# Bolt.net
KiCad netlist of a schematic drawn in EAGLE
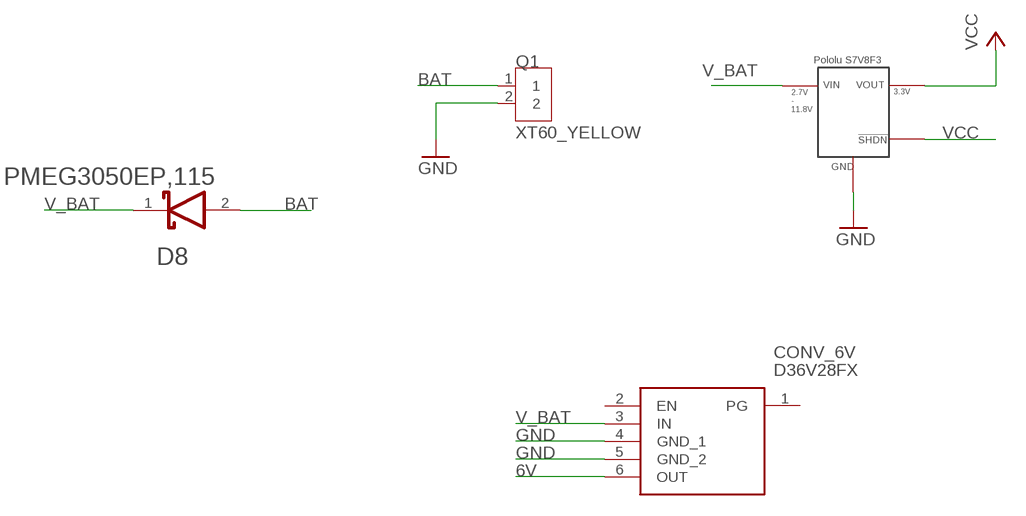
[diagram p0: schematic, sheet 1]
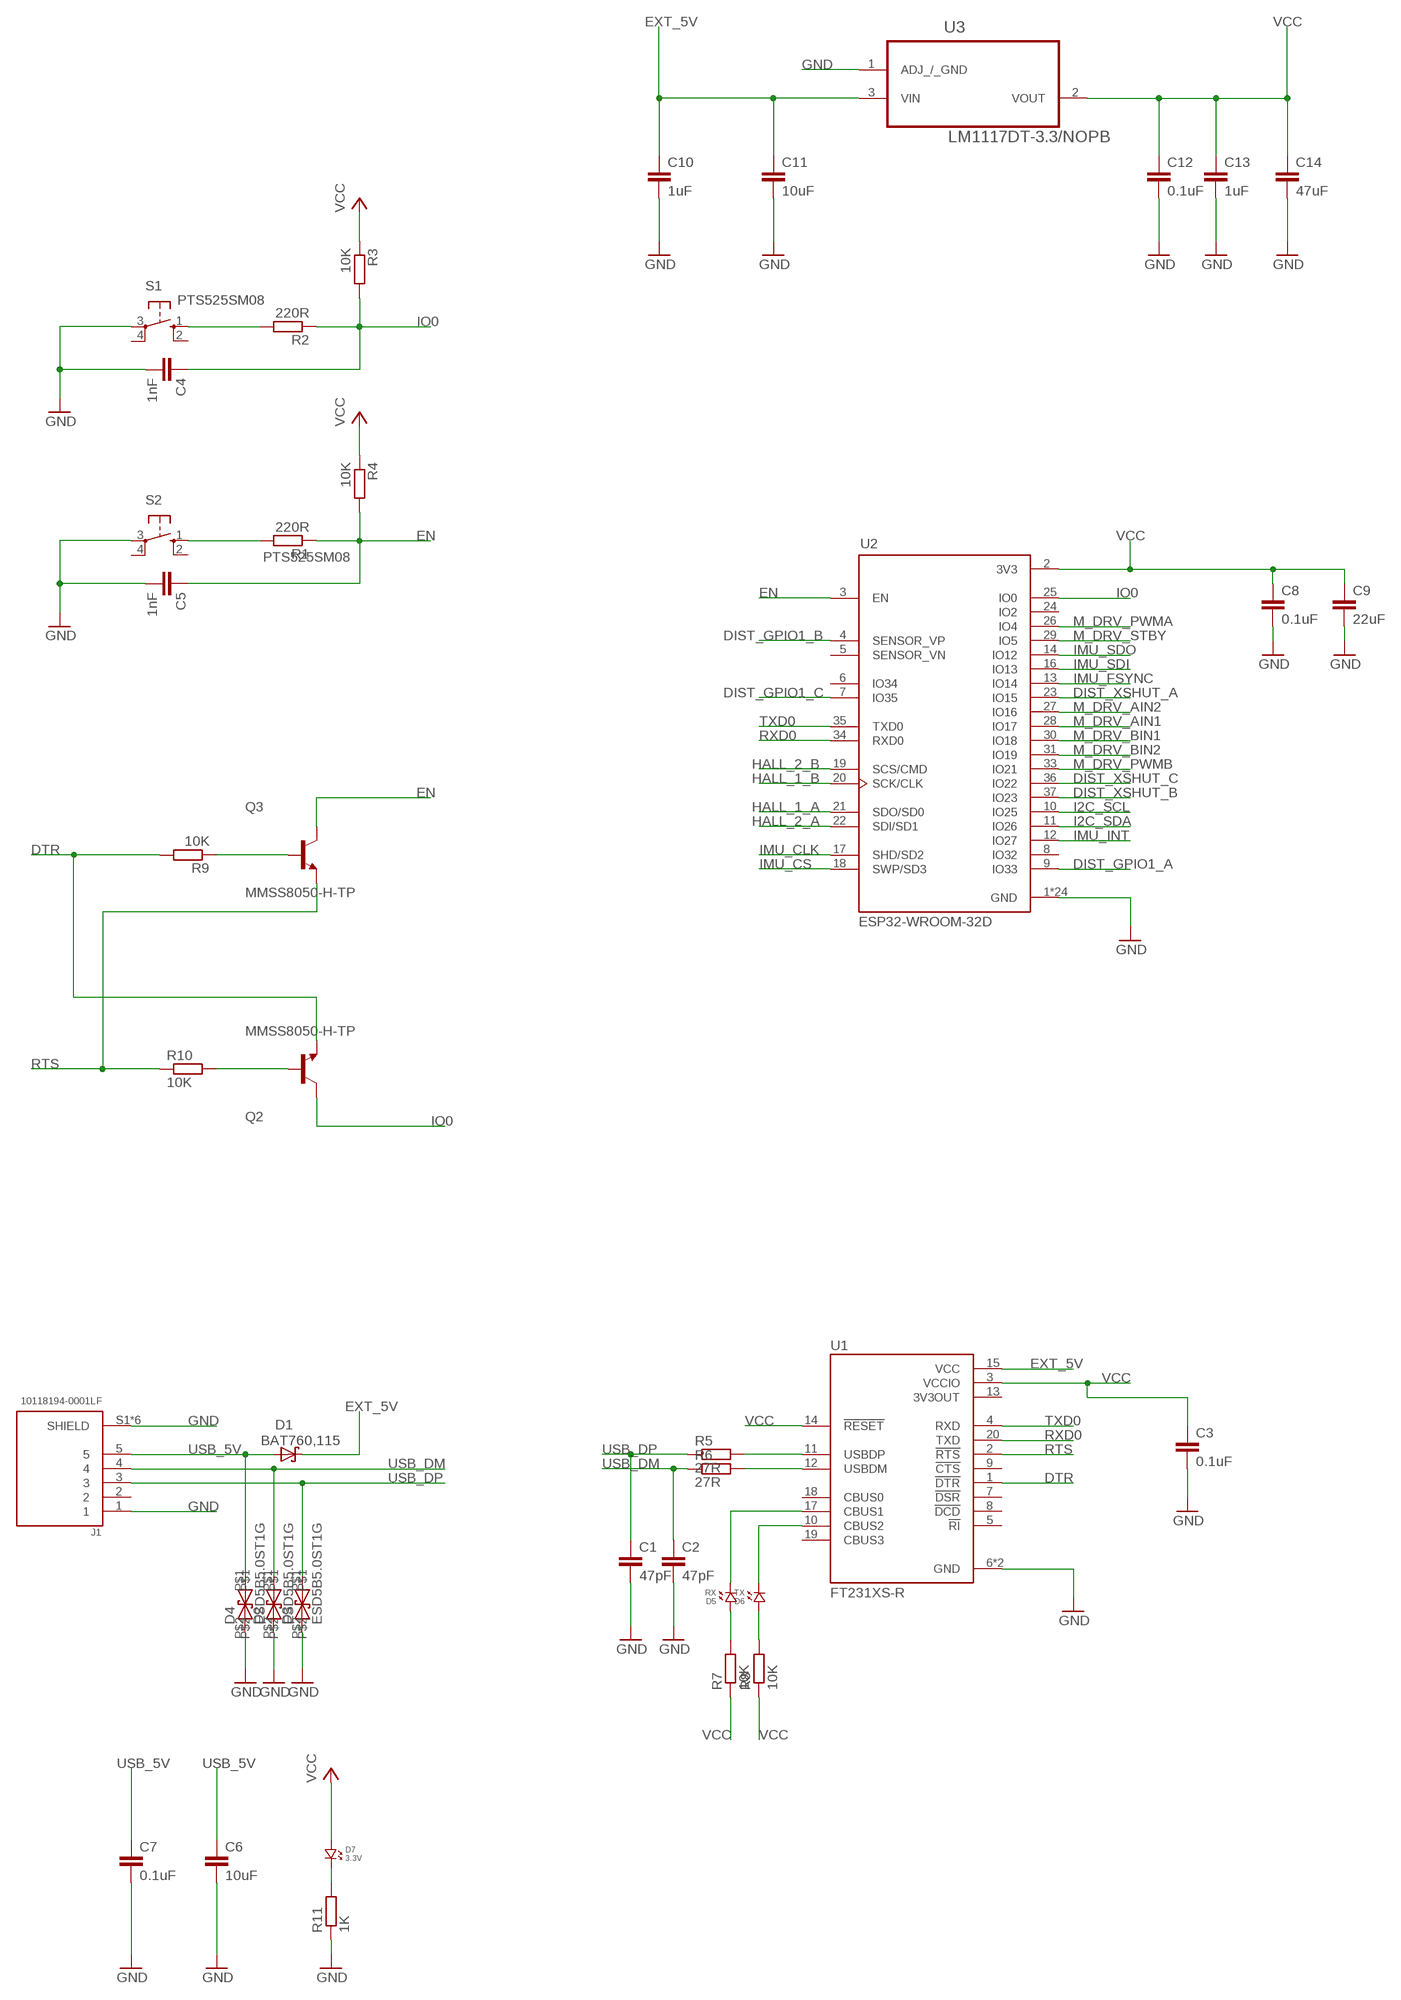
[diagram p1: schematic, sheet 2]
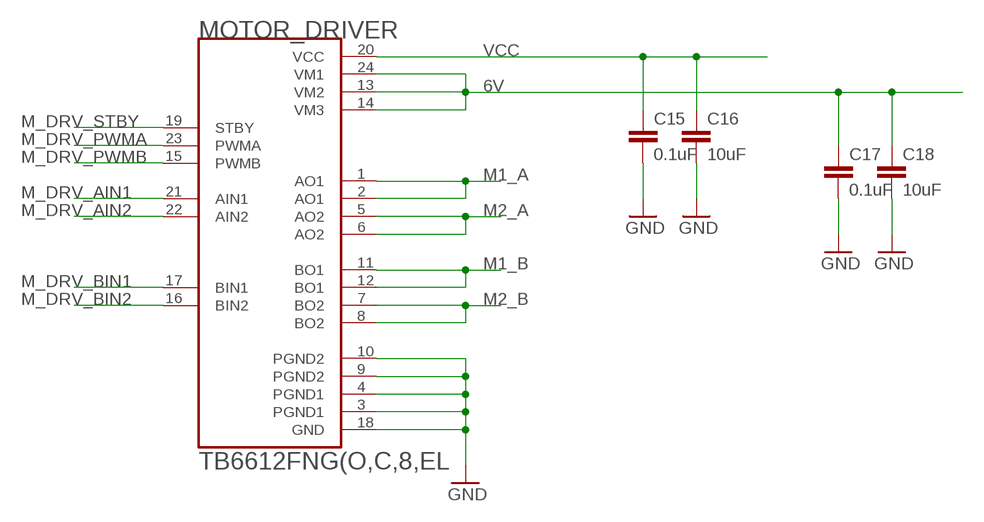
[diagram p2: schematic, sheet 3]
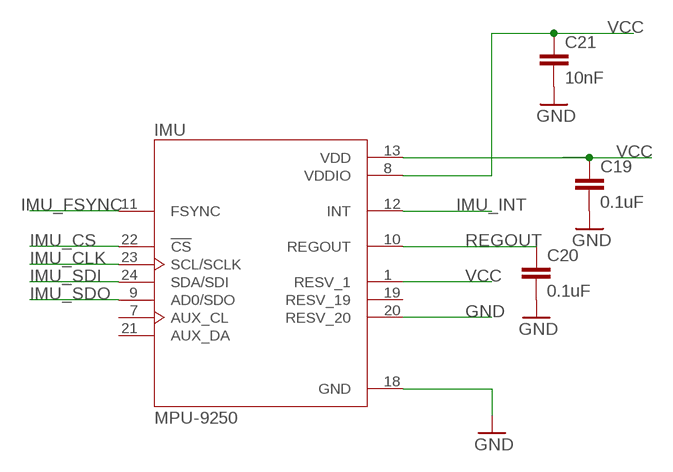
[diagram p3: schematic, sheet 4]
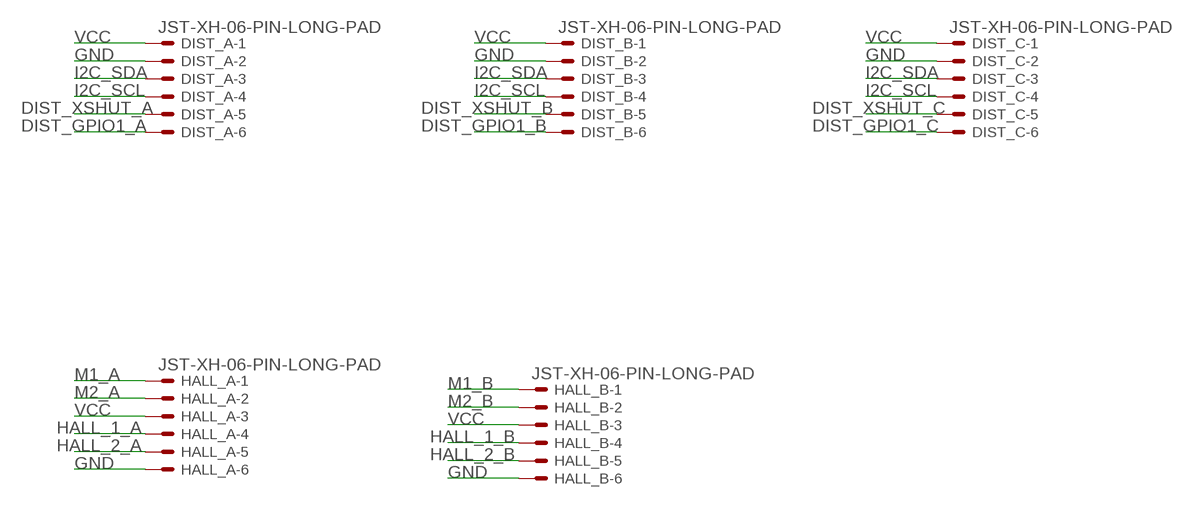
[diagram p4: schematic, sheet 5]

(export (version "E")
  (design (tool "Eeschema 10.0.6"))
  (components
    (comp (ref "DIST_A")
      (value "JST-XH-06-PIN-LONG-PAD")
      (footprint "eagle-import:JST-XH-06-PACKAGE-LONG-PAD")
      (libsource (lib "eagle-import") (part "JST-XH-06-PIN-LONG-PAD"))
    )
    (comp (ref "DIST_B")
      (value "JST-XH-06-PIN-LONG-PAD")
      (footprint "eagle-import:JST-XH-06-PACKAGE-LONG-PAD")
      (libsource (lib "eagle-import") (part "JST-XH-06-PIN-LONG-PAD"))
    )
    (comp (ref "DIST_C")
      (value "JST-XH-06-PIN-LONG-PAD")
      (footprint "eagle-import:JST-XH-06-PACKAGE-LONG-PAD")
      (libsource (lib "eagle-import") (part "JST-XH-06-PIN-LONG-PAD"))
    )
    (comp (ref "HALL_A")
      (value "JST-XH-06-PIN-LONG-PAD")
      (footprint "eagle-import:JST-XH-06-PACKAGE-LONG-PAD")
      (libsource (lib "eagle-import") (part "JST-XH-06-PIN-LONG-PAD"))
    )
    (comp (ref "HALL_B")
      (value "JST-XH-06-PIN-LONG-PAD")
      (footprint "eagle-import:JST-XH-06-PACKAGE-LONG-PAD")
      (libsource (lib "eagle-import") (part "JST-XH-06-PIN-LONG-PAD"))
    )
    (comp (ref "C1")
      (value "47pF")
      (footprint "eagle-import:C0805K")
      (libsource (lib "eagle-import") (part "C-EUC0805K"))
    )
    (comp (ref "C2")
      (value "47pF")
      (footprint "eagle-import:C0805K")
      (libsource (lib "eagle-import") (part "C-EUC0805K"))
    )
    (comp (ref "C3")
      (value "0.1uF")
      (footprint "eagle-import:C0805K")
      (libsource (lib "eagle-import") (part "C-EUC0805K"))
    )
    (comp (ref "C4")
      (value "1nF")
      (footprint "eagle-import:C0805K")
      (libsource (lib "eagle-import") (part "C-EUC0805K"))
    )
    (comp (ref "C5")
      (value "1nF")
      (footprint "eagle-import:C0805K")
      (libsource (lib "eagle-import") (part "C-EUC0805K"))
    )
    (comp (ref "C6")
      (value "10uF")
      (footprint "eagle-import:C0805K")
      (libsource (lib "eagle-import") (part "C-EUC0805K"))
    )
    (comp (ref "C7")
      (value "0.1uF")
      (footprint "eagle-import:C0805K")
      (libsource (lib "eagle-import") (part "C-EUC0805K"))
    )
    (comp (ref "C8")
      (value "0.1uF")
      (footprint "eagle-import:C0805K")
      (libsource (lib "eagle-import") (part "C-EUC0805K"))
    )
    (comp (ref "C9")
      (value "22uF")
      (footprint "eagle-import:C0805K")
      (libsource (lib "eagle-import") (part "C-EUC0805K"))
    )
    (comp (ref "C10")
      (value "1uF")
      (footprint "eagle-import:C0805K")
      (libsource (lib "eagle-import") (part "C-EUC0805K"))
    )
    (comp (ref "C11")
      (value "10uF")
      (footprint "eagle-import:C0805K")
      (libsource (lib "eagle-import") (part "C-EUC0805K"))
    )
    (comp (ref "C12")
      (value "0.1uF")
      (footprint "eagle-import:C0805K")
      (libsource (lib "eagle-import") (part "C-EUC0805K"))
    )
    (comp (ref "C13")
      (value "1uF")
      (footprint "eagle-import:C0805K")
      (libsource (lib "eagle-import") (part "C-EUC0805K"))
    )
    (comp (ref "C14")
      (value "47uF")
      (footprint "eagle-import:C0805K")
      (libsource (lib "eagle-import") (part "C-EUC0805K"))
    )
    (comp (ref "D1")
      (value "BAT760,115")
      (footprint "eagle-import:SOD323(F)")
      (fields (field (name "MF") "Nexperia USA"))
      (libsource (lib "eagle-import") (part "BAT760,115"))
    )
    (comp (ref "D2")
      (value "ESD5B5.0ST1G")
      (footprint "eagle-import:SOD-523")
      (fields (field (name "MF") "Nexperia USA") (field (name "MP") "BAT760,115"))
      (libsource (lib "eagle-import") (part "ESD5B5.0ST1G"))
    )
    (comp (ref "D3")
      (value "ESD5B5.0ST1G")
      (footprint "eagle-import:SOD-523")
      (fields (field (name "MF") "Nexperia USA") (field (name "MP") "BAT760,115"))
      (libsource (lib "eagle-import") (part "ESD5B5.0ST1G"))
    )
    (comp (ref "D4")
      (value "ESD5B5.0ST1G")
      (footprint "eagle-import:SOD-523")
      (fields (field (name "MF") "Nexperia USA") (field (name "MP") "BAT760,115"))
      (libsource (lib "eagle-import") (part "ESD5B5.0ST1G"))
    )
    (comp (ref "D5")
      (value "RX")
      (footprint "eagle-import:0805.LED")
      (libsource (lib "eagle-import") (part "LED.0805"))
    )
    (comp (ref "D6")
      (value "TX")
      (footprint "eagle-import:0805.LED")
      (libsource (lib "eagle-import") (part "LED.0805"))
    )
    (comp (ref "D7")
      (value "3.3V")
      (footprint "eagle-import:0805.LED")
      (libsource (lib "eagle-import") (part "LED.0805"))
    )
    (comp (ref "J1")
      (value "10118194-0001LF")
      (footprint "eagle-import:AMPHENOL_10118194-0001LF")
      (fields (field (name "MF") "Amphenol ICC (FCI)"))
      (libsource (lib "eagle-import") (part "10118194-0001LF"))
    )
    (comp (ref "Q2")
      (value "MMSS8050-H-TP")
      (footprint "eagle-import:TRANS_MMSS8050-H-TP")
      (fields (field (name "MF") "Micro Commercial"))
      (libsource (lib "eagle-import") (part "MMSS8050-H-TP"))
    )
    (comp (ref "Q3")
      (value "MMSS8050-H-TP")
      (footprint "eagle-import:TRANS_MMSS8050-H-TP")
      (fields (field (name "MF") "Micro Commercial"))
      (libsource (lib "eagle-import") (part "MMSS8050-H-TP"))
    )
    (comp (ref "R1")
      (value "220R")
      (footprint "eagle-import:R0805")
      (libsource (lib "eagle-import") (part "R-EU_R0805"))
    )
    (comp (ref "R2")
      (value "220R")
      (footprint "eagle-import:R0805")
      (libsource (lib "eagle-import") (part "R-EU_R0805"))
    )
    (comp (ref "R3")
      (value "10K")
      (footprint "eagle-import:R0805")
      (libsource (lib "eagle-import") (part "R-EU_R0805"))
    )
    (comp (ref "R4")
      (value "10K")
      (footprint "eagle-import:R0805")
      (libsource (lib "eagle-import") (part "R-EU_R0805"))
    )
    (comp (ref "R5")
      (value "27R")
      (footprint "eagle-import:R0805")
      (libsource (lib "eagle-import") (part "R-EU_R0805"))
    )
    (comp (ref "R6")
      (value "27R")
      (footprint "eagle-import:R0805")
      (libsource (lib "eagle-import") (part "R-EU_R0805"))
    )
    (comp (ref "R7")
      (value "10K")
      (footprint "eagle-import:R0805")
      (libsource (lib "eagle-import") (part "R-EU_R0805"))
    )
    (comp (ref "R8")
      (value "10K")
      (footprint "eagle-import:R0805")
      (libsource (lib "eagle-import") (part "R-EU_R0805"))
    )
    (comp (ref "R9")
      (value "10K")
      (footprint "eagle-import:R0805")
      (libsource (lib "eagle-import") (part "R-EU_R0805"))
    )
    (comp (ref "R10")
      (value "10K")
      (footprint "eagle-import:R0805")
      (libsource (lib "eagle-import") (part "R-EU_R0805"))
    )
    (comp (ref "R11")
      (value "1K")
      (footprint "eagle-import:R0805")
      (libsource (lib "eagle-import") (part "R-EU_R0805"))
    )
    (comp (ref "S1")
      (value "PTS525SM08")
      (footprint "eagle-import:SM08")
      (fields (field (name "MF") "C&K Components") (field (name "MPN") "PTS525SM08SMTR2LFS"))
      (libsource (lib "eagle-import") (part "PTS52508SM"))
    )
    (comp (ref "S2")
      (value "PTS525SM08")
      (footprint "eagle-import:SM08")
      (fields (field (name "MF") "C&K Components") (field (name "MPN") "PTS525SM08SMTR2LFS"))
      (libsource (lib "eagle-import") (part "PTS52508SM"))
    )
    (comp (ref "U1")
      (value "FT231XS-R")
      (footprint "eagle-import:SOP63P599X175-20N")
      (fields (field (name "DIGI-KEY_PART_NUMBER") "768-1129-1-ND") (field (name "MF") "FTDI,"))
      (libsource (lib "eagle-import") (part "FT231XS-R"))
    )
    (comp (ref "U2")
      (value "ESP32-WROOM-32D")
      (footprint "eagle-import:MODULE_ESP32-WROOM-32D")
      (fields (field (name "MF") "Espressif Systems"))
      (libsource (lib "eagle-import") (part "ESP32-WROOM-32D"))
    )
    (comp (ref "U3")
      (value "LM1117DT-3.3/NOPB")
      (footprint "eagle-import:TO228P970X238-3N")
      (fields (field (name "MF") "Texas Instruments"))
      (libsource (lib "eagle-import") (part "LM1117DT-3.3/NOPB"))
    )
    (comp (ref "C19")
      (value "0.1uF")
      (footprint "eagle-import:C0805K")
      (libsource (lib "eagle-import") (part "C-EUC0805K"))
    )
    (comp (ref "C20")
      (value "0.1uF")
      (footprint "eagle-import:C0805K")
      (libsource (lib "eagle-import") (part "C-EUC0805K"))
    )
    (comp (ref "C21")
      (value "10nF")
      (footprint "eagle-import:C0805K")
      (libsource (lib "eagle-import") (part "C-EUC0805K"))
    )
    (comp (ref "IMU")
      (value "MPU-9250")
      (footprint "eagle-import:QFN40P300X300X105-24N")
      (fields (field (name "MF") "TDK InvenSense"))
      (libsource (lib "eagle-import") (part "MPU-9250"))
    )
    (comp (ref "C15")
      (value "0.1uF")
      (footprint "eagle-import:C0805K")
      (libsource (lib "eagle-import") (part "C-EUC0805K"))
    )
    (comp (ref "C16")
      (value "10uF")
      (footprint "eagle-import:C0805K")
      (libsource (lib "eagle-import") (part "C-EUC0805K"))
    )
    (comp (ref "C17")
      (value "0.1uF")
      (footprint "eagle-import:C0805K")
      (libsource (lib "eagle-import") (part "C-EUC0805K"))
    )
    (comp (ref "C18")
      (value "10uF")
      (footprint "eagle-import:C0805K")
      (libsource (lib "eagle-import") (part "C-EUC0805K"))
    )
    (comp (ref "MOTOR_DRIVER")
      (value "TB6612FNG(O,C,8,EL")
      (footprint "eagle-import:SOP65P760X160-24N")
      (fields (field (name "MF") "Toshiba"))
      (libsource (lib "eagle-import") (part "TB6612FNG(O,C,8,EL"))
    )
    (comp (ref "CONV_3V3")
      (value "S7V8F3")
      (footprint "eagle-import:S7V8F3")
      (libsource (lib "eagle-import") (part "S7V8F3"))
    )
    (comp (ref "CONV_6V")
      (value "D36V28FX")
      (footprint "eagle-import:D36V28FX")
      (libsource (lib "eagle-import") (part "D36V28FX"))
    )
    (comp (ref "D8")
      (value "NEXPERIA_PMEG3050EP,115NEXPERIA_PMEG3050EP,115_0_0")
      (footprint "eagle-import:NEXPERIA_PMEG3050EP,115_0")
      (fields
        (field (name "DIGIKEY_PART_NUMBER") "1727-5317-1-ND")
        (field (name "MF") "Nexperia")
        (field (name "MOUSER_PART_NUMBER") "771-PMEG3050EP115")
      )
      (libsource (lib "eagle-import") (part "NEXPERIA_PMEG3050EP,115NEXPERIA_PMEG3050EP,115_0_0"))
    )
    (comp (ref "Q1")
      (value "XT60_YELLOW")
      (footprint "eagle-import:AMASS_XT60PB-M")
      (fields (field (name "MF") "Pololu") (field (name "MP") "XT60 YELLOW"))
      (libsource (lib "eagle-import") (part "XT60_YELLOW"))
    )
  )
  (nets
    (net (code "1") (name "3V3OUT") (class "Default")
      (node (ref "U1") (pin "13") (pinfunction "3V3OUT_13") (pintype "power_in"))
    )
    (net (code "2") (name "6V") (class "Default")
      (node (ref "C17") (pin "1") (pinfunction "1_1") (pintype "passive"))
      (node (ref "C18") (pin "1") (pinfunction "1_1") (pintype "passive"))
      (node (ref "CONV_6V") (pin "6") (pinfunction "OUT_6") (pintype "bidirectional"))
      (node (ref "MOTOR_DRIVER") (pin "13") (pinfunction "VM2_13") (pintype "power_in"))
      (node (ref "MOTOR_DRIVER") (pin "14") (pinfunction "VM3_14") (pintype "power_in"))
      (node (ref "MOTOR_DRIVER") (pin "24") (pinfunction "VM1_24") (pintype "power_in"))
    )
    (net (code "3") (name "BAT") (class "Default")
      (node (ref "D8") (pin "2") (pinfunction "ANODE_2") (pintype "passive"))
      (node (ref "Q1") (pin "1") (pinfunction "1_1") (pintype "passive"))
    )
    (net (code "4") (name "DIST_GPIO1_A") (class "Default")
      (node (ref "DIST_A") (pin "6") (pinfunction "S_6") (pintype "passive"))
      (node (ref "U2") (pin "9") (pinfunction "IO33_9") (pintype "bidirectional"))
    )
    (net (code "5") (name "DIST_GPIO1_B") (class "Default")
      (node (ref "DIST_B") (pin "6") (pinfunction "S_6") (pintype "passive"))
      (node (ref "U2") (pin "4") (pinfunction "SENSOR_VP_4") (pintype "input"))
    )
    (net (code "6") (name "DIST_GPIO1_C") (class "Default")
      (node (ref "DIST_C") (pin "6") (pinfunction "S_6") (pintype "passive"))
      (node (ref "U2") (pin "7") (pinfunction "IO35_7") (pintype "input"))
    )
    (net (code "7") (name "DIST_XSHUT_A") (class "Default")
      (node (ref "DIST_A") (pin "5") (pinfunction "S_5") (pintype "passive"))
      (node (ref "U2") (pin "23") (pinfunction "IO15_23") (pintype "bidirectional"))
    )
    (net (code "8") (name "DIST_XSHUT_B") (class "Default")
      (node (ref "DIST_B") (pin "5") (pinfunction "S_5") (pintype "passive"))
      (node (ref "U2") (pin "37") (pinfunction "IO23_37") (pintype "bidirectional"))
    )
    (net (code "9") (name "DIST_XSHUT_C") (class "Default")
      (node (ref "DIST_C") (pin "5") (pinfunction "S_5") (pintype "passive"))
      (node (ref "U2") (pin "36") (pinfunction "IO22_36") (pintype "bidirectional"))
    )
    (net (code "10") (name "DTR") (class "Default")
      (node (ref "Q2") (pin "2") (pinfunction "E_2") (pintype "passive"))
      (node (ref "R9") (pin "2") (pinfunction "2_2") (pintype "passive"))
      (node (ref "U1") (pin "1") (pinfunction "~{DTR}_1") (pintype "output"))
    )
    (net (code "11") (name "EN") (class "Default")
      (node (ref "C5") (pin "1") (pinfunction "1_1") (pintype "passive"))
      (node (ref "Q3") (pin "3") (pinfunction "C_3") (pintype "passive"))
      (node (ref "R1") (pin "1") (pinfunction "1_1") (pintype "passive"))
      (node (ref "R4") (pin "2") (pinfunction "2_2") (pintype "passive"))
      (node (ref "U2") (pin "3") (pinfunction "EN_3") (pintype "input"))
    )
    (net (code "12") (name "EXT_5V") (class "Default")
      (node (ref "C10") (pin "1") (pinfunction "1_1") (pintype "passive"))
      (node (ref "C11") (pin "1") (pinfunction "1_1") (pintype "passive"))
      (node (ref "D1") (pin "1") (pinfunction "K_1") (pintype "passive"))
      (node (ref "U1") (pin "15") (pinfunction "VCC_15") (pintype "power_in"))
      (node (ref "U3") (pin "3") (pinfunction "VIN_3") (pintype "input"))
    )
    (net (code "13") (name "GND") (class "Default")
      (node (ref "C1") (pin "2") (pinfunction "2_2") (pintype "passive"))
      (node (ref "C10") (pin "2") (pinfunction "2_2") (pintype "passive"))
      (node (ref "C11") (pin "2") (pinfunction "2_2") (pintype "passive"))
      (node (ref "C12") (pin "2") (pinfunction "2_2") (pintype "passive"))
      (node (ref "C13") (pin "2") (pinfunction "2_2") (pintype "passive"))
      (node (ref "C14") (pin "2") (pinfunction "2_2") (pintype "passive"))
      (node (ref "C15") (pin "2") (pinfunction "2_2") (pintype "passive"))
      (node (ref "C16") (pin "2") (pinfunction "2_2") (pintype "passive"))
      (node (ref "C17") (pin "2") (pinfunction "2_2") (pintype "passive"))
      (node (ref "C18") (pin "2") (pinfunction "2_2") (pintype "passive"))
      (node (ref "C19") (pin "2") (pinfunction "2_2") (pintype "passive"))
      (node (ref "C2") (pin "2") (pinfunction "2_2") (pintype "passive"))
      (node (ref "C20") (pin "2") (pinfunction "2_2") (pintype "passive"))
      (node (ref "C21") (pin "2") (pinfunction "2_2") (pintype "passive"))
      (node (ref "C3") (pin "2") (pinfunction "2_2") (pintype "passive"))
      (node (ref "C4") (pin "2") (pinfunction "2_2") (pintype "passive"))
      (node (ref "C5") (pin "2") (pinfunction "2_2") (pintype "passive"))
      (node (ref "C6") (pin "2") (pinfunction "2_2") (pintype "passive"))
      (node (ref "C7") (pin "2") (pinfunction "2_2") (pintype "passive"))
      (node (ref "C8") (pin "2") (pinfunction "2_2") (pintype "passive"))
      (node (ref "C9") (pin "2") (pinfunction "2_2") (pintype "passive"))
      (node (ref "CONV_3V3") (pin "GND") (pinfunction "GND_GND") (pintype "bidirectional"))
      (node (ref "CONV_6V") (pin "4") (pinfunction "GND_1_4") (pintype "bidirectional"))
      (node (ref "CONV_6V") (pin "5") (pinfunction "GND_2_5") (pintype "bidirectional"))
      (node (ref "D2") (pin "P$2") (pinfunction "P$1_P$2") (pintype "bidirectional"))
      (node (ref "D3") (pin "P$2") (pinfunction "P$1_P$2") (pintype "bidirectional"))
      (node (ref "D4") (pin "P$2") (pinfunction "P$1_P$2") (pintype "bidirectional"))
      (node (ref "DIST_A") (pin "2") (pinfunction "S_2") (pintype "passive"))
      (node (ref "DIST_B") (pin "2") (pinfunction "S_2") (pintype "passive"))
      (node (ref "DIST_C") (pin "2") (pinfunction "S_2") (pintype "passive"))
      (node (ref "HALL_A") (pin "6") (pinfunction "S_6") (pintype "passive"))
      (node (ref "HALL_B") (pin "6") (pinfunction "S_6") (pintype "passive"))
      (node (ref "IMU") (pin "18") (pinfunction "GND_18") (pintype "power_in"))
      (node (ref "IMU") (pin "20") (pinfunction "RESV_20_20") (pintype "passive"))
      (node (ref "J1") (pin "1") (pinfunction "1_1") (pintype "passive"))
      (node (ref "J1") (pin "S1") (pinfunction "SHIELD_S1") (pintype "passive"))
      (node (ref "J1") (pin "S2") (pinfunction "SHIELD_S2") (pintype "passive"))
      (node (ref "J1") (pin "S3") (pinfunction "SHIELD_S3") (pintype "passive"))
      (node (ref "J1") (pin "S4") (pinfunction "SHIELD_S4") (pintype "passive"))
      (node (ref "J1") (pin "S5") (pinfunction "SHIELD_S5") (pintype "passive"))
      (node (ref "J1") (pin "S6") (pinfunction "SHIELD_S6") (pintype "passive"))
      (node (ref "MOTOR_DRIVER") (pin "10") (pinfunction "PGND2_10") (pintype "passive"))
      (node (ref "MOTOR_DRIVER") (pin "18") (pinfunction "GND_18") (pintype "passive"))
      (node (ref "MOTOR_DRIVER") (pin "3") (pinfunction "PGND1_3") (pintype "passive"))
      (node (ref "MOTOR_DRIVER") (pin "4") (pinfunction "PGND1_4") (pintype "passive"))
      (node (ref "MOTOR_DRIVER") (pin "9") (pinfunction "PGND2_9") (pintype "passive"))
      (node (ref "Q1") (pin "2") (pinfunction "2_2") (pintype "passive"))
      (node (ref "R11") (pin "1") (pinfunction "1_1") (pintype "passive"))
      (node (ref "S1") (pin "3") (pinfunction "P_3") (pintype "passive"))
      (node (ref "S2") (pin "3") (pinfunction "P_3") (pintype "passive"))
      (node (ref "U1") (pin "16") (pinfunction "GND_16") (pintype "power_in"))
      (node (ref "U1") (pin "6") (pinfunction "GND_6") (pintype "power_in"))
      (node (ref "U2") (pin "1") (pinfunction "GND_1") (pintype "power_in"))
      (node (ref "U2") (pin "15") (pinfunction "GND_15") (pintype "power_in"))
      (node (ref "U2") (pin "38") (pinfunction "GND_38") (pintype "power_in"))
      (node (ref "U2") (pin "39_1") (pinfunction "GND_39_1") (pintype "power_in"))
      (node (ref "U2") (pin "39_10") (pinfunction "GND_39_10") (pintype "power_in"))
      (node (ref "U2") (pin "39_11") (pinfunction "GND_39_11") (pintype "power_in"))
      (node (ref "U2") (pin "39_12") (pinfunction "GND_39_12") (pintype "power_in"))
      (node (ref "U2") (pin "39_13") (pinfunction "GND_39_13") (pintype "power_in"))
      (node (ref "U2") (pin "39_14") (pinfunction "GND_39_14") (pintype "power_in"))
      (node (ref "U2") (pin "39_15") (pinfunction "GND_39_15") (pintype "power_in"))
      (node (ref "U2") (pin "39_16") (pinfunction "GND_39_16") (pintype "power_in"))
      (node (ref "U2") (pin "39_17") (pinfunction "GND_39_17") (pintype "power_in"))
      (node (ref "U2") (pin "39_18") (pinfunction "GND_39_18") (pintype "power_in"))
      (node (ref "U2") (pin "39_19") (pinfunction "GND_39_19") (pintype "power_in"))
      (node (ref "U2") (pin "39_2") (pinfunction "GND_39_2") (pintype "power_in"))
      (node (ref "U2") (pin "39_20") (pinfunction "GND_39_20") (pintype "power_in"))
      (node (ref "U2") (pin "39_21") (pinfunction "GND_39_21") (pintype "power_in"))
      (node (ref "U2") (pin "39_3") (pinfunction "GND_39_3") (pintype "power_in"))
      (node (ref "U2") (pin "39_4") (pinfunction "GND_39_4") (pintype "power_in"))
      (node (ref "U2") (pin "39_5") (pinfunction "GND_39_5") (pintype "power_in"))
      (node (ref "U2") (pin "39_6") (pinfunction "GND_39_6") (pintype "power_in"))
      (node (ref "U2") (pin "39_7") (pinfunction "GND_39_7") (pintype "power_in"))
      (node (ref "U2") (pin "39_8") (pinfunction "GND_39_8") (pintype "power_in"))
      (node (ref "U2") (pin "39_9") (pinfunction "GND_39_9") (pintype "power_in"))
      (node (ref "U3") (pin "1") (pinfunction "ADJ_/_GND_1") (pintype "power_in"))
    )
    (net (code "14") (name "HALL_1_A") (class "Default")
      (node (ref "HALL_A") (pin "4") (pinfunction "S_4") (pintype "passive"))
      (node (ref "U2") (pin "21") (pinfunction "SDO/SD0_21") (pintype "bidirectional"))
    )
    (net (code "15") (name "HALL_1_B") (class "Default")
      (node (ref "HALL_B") (pin "4") (pinfunction "S_4") (pintype "passive"))
      (node (ref "U2") (pin "20") (pinfunction "SCK/CLK_20") (pintype "bidirectional"))
    )
    (net (code "16") (name "HALL_2_A") (class "Default")
      (node (ref "HALL_A") (pin "5") (pinfunction "S_5") (pintype "passive"))
      (node (ref "U2") (pin "22") (pinfunction "SDI/SD1_22") (pintype "bidirectional"))
    )
    (net (code "17") (name "HALL_2_B") (class "Default")
      (node (ref "HALL_B") (pin "5") (pinfunction "S_5") (pintype "passive"))
      (node (ref "U2") (pin "19") (pinfunction "SCS/CMD_19") (pintype "bidirectional"))
    )
    (net (code "18") (name "I2C_SCL") (class "Default")
      (node (ref "DIST_A") (pin "4") (pinfunction "S_4") (pintype "passive"))
      (node (ref "DIST_B") (pin "4") (pinfunction "S_4") (pintype "passive"))
      (node (ref "DIST_C") (pin "4") (pinfunction "S_4") (pintype "passive"))
      (node (ref "U2") (pin "10") (pinfunction "IO25_10") (pintype "bidirectional"))
    )
    (net (code "19") (name "I2C_SDA") (class "Default")
      (node (ref "DIST_A") (pin "3") (pinfunction "S_3") (pintype "passive"))
      (node (ref "DIST_B") (pin "3") (pinfunction "S_3") (pintype "passive"))
      (node (ref "DIST_C") (pin "3") (pinfunction "S_3") (pintype "passive"))
      (node (ref "U2") (pin "11") (pinfunction "IO26_11") (pintype "bidirectional"))
    )
    (net (code "20") (name "IMU_CLK") (class "Default")
      (node (ref "IMU") (pin "23") (pinfunction "SCL/SCLK_23") (pintype "input"))
      (node (ref "U2") (pin "17") (pinfunction "SHD/SD2_17") (pintype "bidirectional"))
    )
    (net (code "21") (name "IMU_CS") (class "Default")
      (node (ref "IMU") (pin "22") (pinfunction "~{CS}_22") (pintype "input"))
      (node (ref "U2") (pin "18") (pinfunction "SWP/SD3_18") (pintype "bidirectional"))
    )
    (net (code "22") (name "IMU_FSYNC") (class "Default")
      (node (ref "IMU") (pin "11") (pinfunction "FSYNC_11") (pintype "input"))
      (node (ref "U2") (pin "13") (pinfunction "IO14_13") (pintype "bidirectional"))
    )
    (net (code "23") (name "IMU_INT") (class "Default")
      (node (ref "IMU") (pin "12") (pinfunction "INT_12") (pintype "output"))
      (node (ref "U2") (pin "12") (pinfunction "IO27_12") (pintype "bidirectional"))
    )
    (net (code "24") (name "IMU_SDI") (class "Default")
      (node (ref "IMU") (pin "24") (pinfunction "SDA/SDI_24") (pintype "bidirectional"))
      (node (ref "U2") (pin "16") (pinfunction "IO13_16") (pintype "bidirectional"))
    )
    (net (code "25") (name "IMU_SDO") (class "Default")
      (node (ref "IMU") (pin "9") (pinfunction "AD0/SDO_9") (pintype "output"))
      (node (ref "U2") (pin "14") (pinfunction "IO12_14") (pintype "bidirectional"))
    )
    (net (code "26") (name "IO0") (class "Default")
      (node (ref "C4") (pin "1") (pinfunction "1_1") (pintype "passive"))
      (node (ref "Q2") (pin "3") (pinfunction "C_3") (pintype "passive"))
      (node (ref "R2") (pin "1") (pinfunction "1_1") (pintype "passive"))
      (node (ref "R3") (pin "2") (pinfunction "2_2") (pintype "passive"))
      (node (ref "U2") (pin "25") (pinfunction "IO0_25") (pintype "bidirectional"))
    )
    (net (code "27") (name "M1_A") (class "Default")
      (node (ref "HALL_A") (pin "1") (pinfunction "S_1") (pintype "passive"))
      (node (ref "MOTOR_DRIVER") (pin "1") (pinfunction "AO1_1") (pintype "output"))
      (node (ref "MOTOR_DRIVER") (pin "2") (pinfunction "AO1_2") (pintype "output"))
    )
    (net (code "28") (name "M1_B") (class "Default")
      (node (ref "HALL_B") (pin "1") (pinfunction "S_1") (pintype "passive"))
      (node (ref "MOTOR_DRIVER") (pin "11") (pinfunction "BO1_11") (pintype "output"))
      (node (ref "MOTOR_DRIVER") (pin "12") (pinfunction "BO1_12") (pintype "output"))
    )
    (net (code "29") (name "M2_A") (class "Default")
      (node (ref "HALL_A") (pin "2") (pinfunction "S_2") (pintype "passive"))
      (node (ref "MOTOR_DRIVER") (pin "5") (pinfunction "AO2_5") (pintype "output"))
      (node (ref "MOTOR_DRIVER") (pin "6") (pinfunction "AO2_6") (pintype "output"))
    )
    (net (code "30") (name "M2_B") (class "Default")
      (node (ref "HALL_B") (pin "2") (pinfunction "S_2") (pintype "passive"))
      (node (ref "MOTOR_DRIVER") (pin "7") (pinfunction "BO2_7") (pintype "output"))
      (node (ref "MOTOR_DRIVER") (pin "8") (pinfunction "BO2_8") (pintype "output"))
    )
    (net (code "31") (name "M_DRV_AIN1") (class "Default")
      (node (ref "MOTOR_DRIVER") (pin "21") (pinfunction "AIN1_21") (pintype "input"))
      (node (ref "U2") (pin "28") (pinfunction "IO17_28") (pintype "bidirectional"))
    )
    (net (code "32") (name "M_DRV_AIN2") (class "Default")
      (node (ref "MOTOR_DRIVER") (pin "22") (pinfunction "AIN2_22") (pintype "input"))
      (node (ref "U2") (pin "27") (pinfunction "IO16_27") (pintype "bidirectional"))
    )
    (net (code "33") (name "M_DRV_BIN1") (class "Default")
      (node (ref "MOTOR_DRIVER") (pin "17") (pinfunction "BIN1_17") (pintype "input"))
      (node (ref "U2") (pin "30") (pinfunction "IO18_30") (pintype "bidirectional"))
    )
    (net (code "34") (name "M_DRV_BIN2") (class "Default")
      (node (ref "MOTOR_DRIVER") (pin "16") (pinfunction "BIN2_16") (pintype "input"))
      (node (ref "U2") (pin "31") (pinfunction "IO19_31") (pintype "bidirectional"))
    )
    (net (code "35") (name "M_DRV_PWMA") (class "Default")
      (node (ref "MOTOR_DRIVER") (pin "23") (pinfunction "PWMA_23") (pintype "input"))
      (node (ref "U2") (pin "26") (pinfunction "IO4_26") (pintype "bidirectional"))
    )
    (net (code "36") (name "M_DRV_PWMB") (class "Default")
      (node (ref "MOTOR_DRIVER") (pin "15") (pinfunction "PWMB_15") (pintype "input"))
      (node (ref "U2") (pin "33") (pinfunction "IO21_33") (pintype "bidirectional"))
    )
    (net (code "37") (name "M_DRV_STBY") (class "Default")
      (node (ref "MOTOR_DRIVER") (pin "19") (pinfunction "STBY_19") (pintype "input"))
      (node (ref "U2") (pin "29") (pinfunction "IO5_29") (pintype "bidirectional"))
    )
    (net (code "38") (name "Net-(D5-1)") (class "Default")
      (node (ref "D5") (pin "P$1") (pinfunction "1_P$1") (pintype "bidirectional"))
      (node (ref "R7") (pin "2") (pinfunction "2_2") (pintype "passive"))
    )
    (net (code "39") (name "Net-(D5-2)") (class "Default")
      (node (ref "D5") (pin "P$2") (pinfunction "2_P$2") (pintype "bidirectional"))
      (node (ref "U1") (pin "17") (pinfunction "CBUS1_17") (pintype "bidirectional"))
    )
    (net (code "40") (name "Net-(D6-1)") (class "Default")
      (node (ref "D6") (pin "P$1") (pinfunction "1_P$1") (pintype "bidirectional"))
      (node (ref "R8") (pin "2") (pinfunction "2_2") (pintype "passive"))
    )
    (net (code "41") (name "Net-(D6-2)") (class "Default")
      (node (ref "D6") (pin "P$2") (pinfunction "2_P$2") (pintype "bidirectional"))
      (node (ref "U1") (pin "10") (pinfunction "CBUS2_10") (pintype "bidirectional"))
    )
    (net (code "42") (name "Net-(D7-2)") (class "Default")
      (node (ref "D7") (pin "P$2") (pinfunction "2_P$2") (pintype "bidirectional"))
      (node (ref "R11") (pin "2") (pinfunction "2_2") (pintype "passive"))
    )
    (net (code "43") (name "Net-(Q2-B)") (class "Default")
      (node (ref "Q2") (pin "1") (pinfunction "B_1") (pintype "passive"))
      (node (ref "R10") (pin "2") (pinfunction "2_2") (pintype "passive"))
    )
    (net (code "44") (name "Net-(Q3-B)") (class "Default")
      (node (ref "Q3") (pin "1") (pinfunction "B_1") (pintype "passive"))
      (node (ref "R9") (pin "1") (pinfunction "1_1") (pintype "passive"))
    )
    (net (code "45") (name "Net-(R1-Pad2)") (class "Default")
      (node (ref "R1") (pin "2") (pinfunction "2_2") (pintype "passive"))
      (node (ref "S2") (pin "1") (pinfunction "S_1") (pintype "passive"))
    )
    (net (code "46") (name "Net-(R2-Pad2)") (class "Default")
      (node (ref "R2") (pin "2") (pinfunction "2_2") (pintype "passive"))
      (node (ref "S1") (pin "1") (pinfunction "S_1") (pintype "passive"))
    )
    (net (code "47") (name "Net-(U1-USBDM)") (class "Default")
      (node (ref "R6") (pin "2") (pinfunction "2_2") (pintype "passive"))
      (node (ref "U1") (pin "12") (pinfunction "USBDM_12") (pintype "input"))
    )
    (net (code "48") (name "Net-(U1-USBDP)") (class "Default")
      (node (ref "R5") (pin "2") (pinfunction "2_2") (pintype "passive"))
      (node (ref "U1") (pin "11") (pinfunction "USBDP_11") (pintype "input"))
    )
    (net (code "49") (name "REGOUT") (class "Default")
      (node (ref "C20") (pin "1") (pinfunction "1_1") (pintype "passive"))
      (node (ref "IMU") (pin "10") (pinfunction "REGOUT_10") (pintype "output"))
    )
    (net (code "50") (name "RTS") (class "Default")
      (node (ref "Q3") (pin "2") (pinfunction "E_2") (pintype "passive"))
      (node (ref "R10") (pin "1") (pinfunction "1_1") (pintype "passive"))
      (node (ref "U1") (pin "2") (pinfunction "~{RTS}_2") (pintype "output"))
    )
    (net (code "51") (name "RXD0") (class "Default")
      (node (ref "U1") (pin "20") (pinfunction "TXD_20") (pintype "output"))
      (node (ref "U2") (pin "34") (pinfunction "RXD0_34") (pintype "bidirectional"))
    )
    (net (code "52") (name "TXD0") (class "Default")
      (node (ref "U1") (pin "4") (pinfunction "RXD_4") (pintype "input"))
      (node (ref "U2") (pin "35") (pinfunction "TXD0_35") (pintype "bidirectional"))
    )
    (net (code "53") (name "USB_5V") (class "Default")
      (node (ref "C6") (pin "1") (pinfunction "1_1") (pintype "passive"))
      (node (ref "C7") (pin "1") (pinfunction "1_1") (pintype "passive"))
      (node (ref "D1") (pin "2") (pinfunction "A_2") (pintype "passive"))
      (node (ref "D4") (pin "P$1") (pinfunction "P$2_P$1") (pintype "bidirectional"))
      (node (ref "J1") (pin "5") (pinfunction "5_5") (pintype "passive"))
    )
    (net (code "54") (name "USB_DM") (class "Default")
      (node (ref "C2") (pin "1") (pinfunction "1_1") (pintype "passive"))
      (node (ref "D2") (pin "P$1") (pinfunction "P$2_P$1") (pintype "bidirectional"))
      (node (ref "J1") (pin "4") (pinfunction "4_4") (pintype "passive"))
      (node (ref "R6") (pin "1") (pinfunction "1_1") (pintype "passive"))
    )
    (net (code "55") (name "USB_DP") (class "Default")
      (node (ref "C1") (pin "1") (pinfunction "1_1") (pintype "passive"))
      (node (ref "D3") (pin "P$1") (pinfunction "P$2_P$1") (pintype "bidirectional"))
      (node (ref "J1") (pin "3") (pinfunction "3_3") (pintype "passive"))
      (node (ref "R5") (pin "1") (pinfunction "1_1") (pintype "passive"))
    )
    (net (code "56") (name "VCC") (class "Default")
      (node (ref "C12") (pin "1") (pinfunction "1_1") (pintype "passive"))
      (node (ref "C13") (pin "1") (pinfunction "1_1") (pintype "passive"))
      (node (ref "C14") (pin "1") (pinfunction "1_1") (pintype "passive"))
      (node (ref "C15") (pin "1") (pinfunction "1_1") (pintype "passive"))
      (node (ref "C16") (pin "1") (pinfunction "1_1") (pintype "passive"))
      (node (ref "C19") (pin "1") (pinfunction "1_1") (pintype "passive"))
      (node (ref "C21") (pin "1") (pinfunction "1_1") (pintype "passive"))
      (node (ref "C3") (pin "1") (pinfunction "1_1") (pintype "passive"))
      (node (ref "C8") (pin "1") (pinfunction "1_1") (pintype "passive"))
      (node (ref "C9") (pin "1") (pinfunction "1_1") (pintype "passive"))
      (node (ref "CONV_3V3") (pin "!SHDN") (pinfunction "~{SHDN}_!SHDN") (pintype "bidirectional"))
      (node (ref "CONV_3V3") (pin "VOUT") (pinfunction "VOUT_VOUT") (pintype "bidirectional"))
      (node (ref "D7") (pin "P$1") (pinfunction "1_P$1") (pintype "bidirectional"))
      (node (ref "DIST_A") (pin "1") (pinfunction "S_1") (pintype "passive"))
      (node (ref "DIST_B") (pin "1") (pinfunction "S_1") (pintype "passive"))
      (node (ref "DIST_C") (pin "1") (pinfunction "S_1") (pintype "passive"))
      (node (ref "HALL_A") (pin "3") (pinfunction "S_3") (pintype "passive"))
      (node (ref "HALL_B") (pin "3") (pinfunction "S_3") (pintype "passive"))
      (node (ref "IMU") (pin "1") (pinfunction "RESV_1_1") (pintype "passive"))
      (node (ref "IMU") (pin "13") (pinfunction "VDD_13") (pintype "power_in"))
      (node (ref "IMU") (pin "8") (pinfunction "VDDIO_8") (pintype "power_in"))
      (node (ref "MOTOR_DRIVER") (pin "20") (pinfunction "VCC_20") (pintype "power_in"))
      (node (ref "R3") (pin "1") (pinfunction "1_1") (pintype "passive"))
      (node (ref "R4") (pin "1") (pinfunction "1_1") (pintype "passive"))
      (node (ref "R7") (pin "1") (pinfunction "1_1") (pintype "passive"))
      (node (ref "R8") (pin "1") (pinfunction "1_1") (pintype "passive"))
      (node (ref "U1") (pin "14") (pinfunction "~{RESET}_14") (pintype "input"))
      (node (ref "U1") (pin "3") (pinfunction "VCCIO_3") (pintype "power_in"))
      (node (ref "U2") (pin "2") (pinfunction "3V3_2") (pintype "power_in"))
      (node (ref "U3") (pin "2") (pinfunction "VOUT_2") (pintype "output"))
    )
    (net (code "57") (name "V_BAT") (class "Default")
      (node (ref "CONV_3V3") (pin "VIN") (pinfunction "VIN_VIN") (pintype "bidirectional"))
      (node (ref "CONV_6V") (pin "3") (pinfunction "IN_3") (pintype "bidirectional"))
      (node (ref "D8") (pin "1") (pinfunction "CATHODE_1") (pintype "passive"))
    )
    (net (code "58") (name "unconnected-(CONV_6V-EN-Pad2)") (class "Default")
      (node (ref "CONV_6V") (pin "2") (pinfunction "EN_2") (pintype "bidirectional"))
    )
    (net (code "59") (name "unconnected-(CONV_6V-PG-Pad1)") (class "Default")
      (node (ref "CONV_6V") (pin "1") (pinfunction "PG_1") (pintype "bidirectional"))
    )
    (net (code "60") (name "unconnected-(IMU-AUX_CL-Pad7)") (class "Default")
      (node (ref "IMU") (pin "7") (pinfunction "AUX_CL_7") (pintype "input"))
    )
    (net (code "61") (name "unconnected-(IMU-AUX_DA-Pad21)") (class "Default")
      (node (ref "IMU") (pin "21") (pinfunction "AUX_DA_21") (pintype "input"))
    )
    (net (code "62") (name "unconnected-(IMU-RESV_19-Pad19)") (class "Default")
      (node (ref "IMU") (pin "19") (pinfunction "RESV_19_19") (pintype "passive"))
    )
    (net (code "63") (name "unconnected-(J1-Pad2)") (class "Default")
      (node (ref "J1") (pin "2") (pinfunction "2_2") (pintype "passive"))
    )
    (net (code "64") (name "unconnected-(S1-P-Pad4)") (class "Default")
      (node (ref "S1") (pin "4") (pinfunction "P_4") (pintype "passive"))
    )
    (net (code "65") (name "unconnected-(S1-S-Pad2)") (class "Default")
      (node (ref "S1") (pin "2") (pinfunction "S_2") (pintype "passive"))
    )
    (net (code "66") (name "unconnected-(S2-P-Pad4)") (class "Default")
      (node (ref "S2") (pin "4") (pinfunction "P_4") (pintype "passive"))
    )
    (net (code "67") (name "unconnected-(S2-S-Pad2)") (class "Default")
      (node (ref "S2") (pin "2") (pinfunction "S_2") (pintype "passive"))
    )
    (net (code "68") (name "unconnected-(U1-CBUS0-Pad18)") (class "Default")
      (node (ref "U1") (pin "18") (pinfunction "CBUS0_18") (pintype "bidirectional"))
    )
    (net (code "69") (name "unconnected-(U1-CBUS3-Pad19)") (class "Default")
      (node (ref "U1") (pin "19") (pinfunction "CBUS3_19") (pintype "bidirectional"))
    )
    (net (code "70") (name "unconnected-(U1-~{CTS}-Pad9)") (class "Default")
      (node (ref "U1") (pin "9") (pinfunction "~{CTS}_9") (pintype "input"))
    )
    (net (code "71") (name "unconnected-(U1-~{DCD}-Pad8)") (class "Default")
      (node (ref "U1") (pin "8") (pinfunction "~{DCD}_8") (pintype "input"))
    )
    (net (code "72") (name "unconnected-(U1-~{DSR}-Pad7)") (class "Default")
      (node (ref "U1") (pin "7") (pinfunction "~{DSR}_7") (pintype "input"))
    )
    (net (code "73") (name "unconnected-(U1-~{RI}-Pad5)") (class "Default")
      (node (ref "U1") (pin "5") (pinfunction "~{RI}_5") (pintype "input"))
    )
    (net (code "74") (name "unconnected-(U2-IO2-Pad24)") (class "Default")
      (node (ref "U2") (pin "24") (pinfunction "IO2_24") (pintype "bidirectional"))
    )
    (net (code "75") (name "unconnected-(U2-IO32-Pad8)") (class "Default")
      (node (ref "U2") (pin "8") (pinfunction "IO32_8") (pintype "bidirectional"))
    )
    (net (code "76") (name "unconnected-(U2-IO34-Pad6)") (class "Default")
      (node (ref "U2") (pin "6") (pinfunction "IO34_6") (pintype "input"))
    )
    (net (code "77") (name "unconnected-(U2-SENSOR_VN-Pad5)") (class "Default")
      (node (ref "U2") (pin "5") (pinfunction "SENSOR_VN_5") (pintype "input"))
    )
  )
)
